# badge.net
KiCad netlist of a schematic drawn in EAGLE
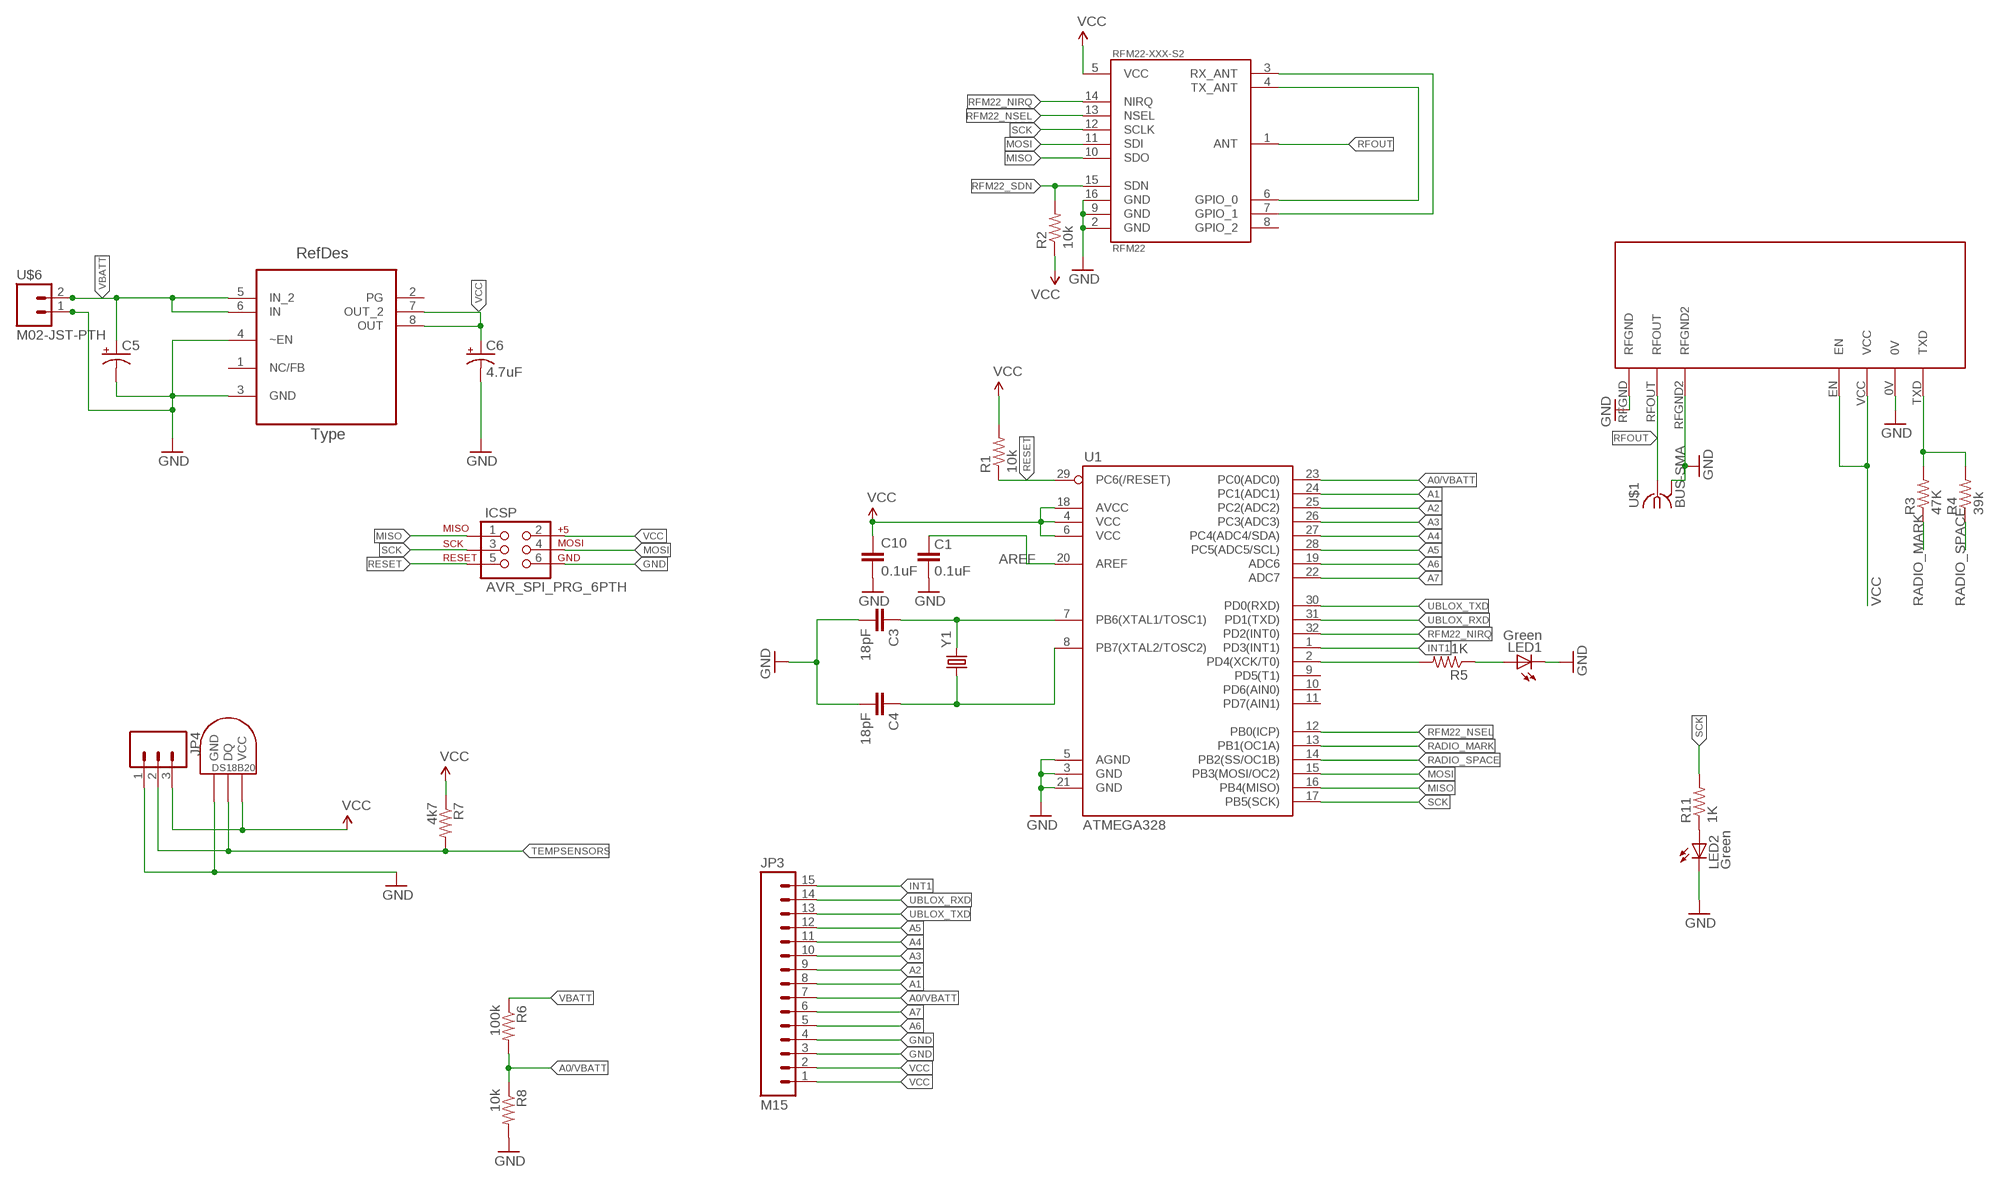
[diagram p0: schematic, sheet 1]

(export (version "E")
  (design (tool "Eeschema 10.0.6"))
  (components
    (comp (ref "C1")
      (value "0.1uF")
      (footprint "eagle-import:0603-CAP")
      (libsource (lib "eagle-import") (part "CAP0603-CAP"))
    )
    (comp (ref "C3")
      (value "18pF")
      (footprint "eagle-import:0603-CAP")
      (libsource (lib "eagle-import") (part "CAP0603-CAP"))
    )
    (comp (ref "C4")
      (value "18pF")
      (footprint "eagle-import:0603-CAP")
      (libsource (lib "eagle-import") (part "CAP0603-CAP"))
    )
    (comp (ref "C5")
      (value "CAP_POL1206-KIT")
      (footprint "eagle-import:EIA3216-KIT")
      (libsource (lib "eagle-import") (part "CAP_POL1206-KIT"))
    )
    (comp (ref "C6")
      (value "4.7uF")
      (footprint "eagle-import:EIA3216-KIT")
      (libsource (lib "eagle-import") (part "CAP_POL1206-KIT"))
    )
    (comp (ref "C10")
      (value "0.1uF")
      (footprint "eagle-import:0603-CAP")
      (libsource (lib "eagle-import") (part "CAP0603-CAP"))
    )
    (comp (ref "ICSP")
      (value "AVR_SPI_PRG_6PTH")
      (footprint "eagle-import:2X3")
      (libsource (lib "eagle-import") (part "AVR_SPI_PRG_6PTH"))
    )
    (comp (ref "JP3")
      (value "M15")
      (footprint "eagle-import:1X15")
      (libsource (lib "eagle-import") (part "M15"))
    )
    (comp (ref "JP4")
      (value "M03PTH")
      (footprint "eagle-import:1X03")
      (libsource (lib "eagle-import") (part "M03PTH"))
    )
    (comp (ref "LED1")
      (value "Green")
      (footprint "eagle-import:LED-0603")
      (libsource (lib "eagle-import") (part "LED0603"))
    )
    (comp (ref "LED2")
      (value "Green")
      (footprint "eagle-import:LED-0603")
      (libsource (lib "eagle-import") (part "LED0603"))
    )
    (comp (ref "NTX2TEMP")
      (value "DS1821")
      (footprint "eagle-import:DS18B20_SOIC")
      (libsource (lib "eagle-import") (part "DS1820SOIC"))
    )
    (comp (ref "R1")
      (value "10k")
      (footprint "eagle-import:0603-RES")
      (libsource (lib "eagle-import") (part "RESISTOR0603-RES"))
    )
    (comp (ref "R2")
      (value "10k")
      (footprint "eagle-import:0603-RES")
      (libsource (lib "eagle-import") (part "RESISTOR0603-RES"))
    )
    (comp (ref "R3")
      (value "47K")
      (footprint "eagle-import:0603-RES")
      (libsource (lib "eagle-import") (part "RESISTOR0603-RES"))
    )
    (comp (ref "R4")
      (value "39k")
      (footprint "eagle-import:0603-RES")
      (libsource (lib "eagle-import") (part "RESISTOR0603-RES"))
    )
    (comp (ref "R5")
      (value "1K")
      (footprint "eagle-import:0603-RES")
      (libsource (lib "eagle-import") (part "RESISTOR0603-RES"))
    )
    (comp (ref "R6")
      (value "100k")
      (footprint "eagle-import:0603-RES")
      (libsource (lib "eagle-import") (part "RESISTOR0603-RES"))
    )
    (comp (ref "R7")
      (value "4k7")
      (footprint "eagle-import:0603-RES")
      (libsource (lib "eagle-import") (part "RESISTOR0603-RES"))
    )
    (comp (ref "R8")
      (value "10k")
      (footprint "eagle-import:0603-RES")
      (libsource (lib "eagle-import") (part "RESISTOR0603-RES"))
    )
    (comp (ref "R11")
      (value "1K")
      (footprint "eagle-import:0603-RES")
      (libsource (lib "eagle-import") (part "RESISTOR0603-RES"))
    )
    (comp (ref "RFM22-XXX-S2")
      (value "RFM22")
      (footprint "eagle-import:RFM22-XXX-S2")
      (libsource (lib "eagle-import") (part "RFM22"))
    )
    (comp (ref "U$1")
      (value "BUS-SMA")
      (footprint "eagle-import:BUS-SMA")
      (libsource (lib "eagle-import") (part "BUS-SMA"))
    )
    (comp (ref "U$4")
      (value "NTX2")
      (footprint "eagle-import:NTX2")
      (libsource (lib "eagle-import") (part "NTX2"))
    )
    (comp (ref "U$6")
      (value "M02-JST-PTH")
      (footprint "eagle-import:M02-JST-PTH")
      (libsource (lib "eagle-import") (part "M02-JST-PTH"))
    )
    (comp (ref "U1")
      (value "ATMEGA328")
      (footprint "eagle-import:TQFP32-08")
      (libsource (lib "eagle-import") (part "ATMEGA168"))
    )
    (comp (ref "U2")
      (value "TPS76633D")
      (footprint "eagle-import:SOIC127P600X175-8N")
      (libsource (lib "eagle-import") (part "TPS76633D"))
    )
    (comp (ref "Y1")
      (value "CRYSTALSMD")
      (footprint "eagle-import:HC49UP")
      (libsource (lib "eagle-import") (part "CRYSTALSMD"))
    )
  )
  (nets
    (net (code "1") (name "/AREF") (class "Default")
      (node (ref "C1") (pin "2") (pinfunction "2_2") (pintype "passive"))
      (node (ref "U1") (pin "20") (pinfunction "AREF_20") (pintype "bidirectional"))
    )
    (net (code "2") (name "A0{slash}VBATT") (class "Default")
      (node (ref "JP3") (pin "7") (pinfunction "7_7") (pintype "passive"))
      (node (ref "R6") (pin "2") (pinfunction "2_2") (pintype "passive"))
      (node (ref "R8") (pin "1") (pinfunction "1_1") (pintype "passive"))
      (node (ref "U1") (pin "23") (pinfunction "PC0(ADC0)_23") (pintype "bidirectional"))
    )
    (net (code "3") (name "A1") (class "Default")
      (node (ref "JP3") (pin "8") (pinfunction "8_8") (pintype "passive"))
      (node (ref "U1") (pin "24") (pinfunction "PC1(ADC1)_24") (pintype "bidirectional"))
    )
    (net (code "4") (name "A2") (class "Default")
      (node (ref "JP3") (pin "9") (pinfunction "9_9") (pintype "passive"))
      (node (ref "U1") (pin "25") (pinfunction "PC2(ADC2)_25") (pintype "bidirectional"))
    )
    (net (code "5") (name "A3") (class "Default")
      (node (ref "JP3") (pin "10") (pinfunction "10_10") (pintype "passive"))
      (node (ref "U1") (pin "26") (pinfunction "PC3(ADC3)_26") (pintype "bidirectional"))
    )
    (net (code "6") (name "A4") (class "Default")
      (node (ref "JP3") (pin "11") (pinfunction "11_11") (pintype "passive"))
      (node (ref "U1") (pin "27") (pinfunction "PC4(ADC4/SDA)_27") (pintype "bidirectional"))
    )
    (net (code "7") (name "A5") (class "Default")
      (node (ref "JP3") (pin "12") (pinfunction "12_12") (pintype "passive"))
      (node (ref "U1") (pin "28") (pinfunction "PC5(ADC5/SCL)_28") (pintype "bidirectional"))
    )
    (net (code "8") (name "A6") (class "Default")
      (node (ref "JP3") (pin "5") (pinfunction "5_5") (pintype "passive"))
      (node (ref "U1") (pin "19") (pinfunction "ADC6_19") (pintype "bidirectional"))
    )
    (net (code "9") (name "A7") (class "Default")
      (node (ref "JP3") (pin "6") (pinfunction "6_6") (pintype "passive"))
      (node (ref "U1") (pin "22") (pinfunction "ADC7_22") (pintype "bidirectional"))
    )
    (net (code "10") (name "GND") (class "Default")
      (node (ref "C1") (pin "1") (pinfunction "1_1") (pintype "passive"))
      (node (ref "C10") (pin "2") (pinfunction "2_2") (pintype "passive"))
      (node (ref "C3") (pin "2") (pinfunction "2_2") (pintype "passive"))
      (node (ref "C4") (pin "2") (pinfunction "2_2") (pintype "passive"))
      (node (ref "C5") (pin "C") (pinfunction "-_C") (pintype "passive"))
      (node (ref "C6") (pin "C") (pinfunction "-_C") (pintype "passive"))
      (node (ref "ICSP") (pin "6") (pinfunction "6_6") (pintype "passive"))
      (node (ref "JP3") (pin "3") (pinfunction "3_3") (pintype "passive"))
      (node (ref "JP3") (pin "4") (pinfunction "4_4") (pintype "passive"))
      (node (ref "JP4") (pin "1") (pinfunction "1_1") (pintype "passive"))
      (node (ref "LED1") (pin "C") (pinfunction "C_C") (pintype "passive"))
      (node (ref "LED2") (pin "C") (pinfunction "C_C") (pintype "passive"))
      (node (ref "NTX2TEMP") (pin "GND") (pinfunction "GND_GND") (pintype "power_in"))
      (node (ref "R8") (pin "2") (pinfunction "2_2") (pintype "passive"))
      (node (ref "RFM22-XXX-S2") (pin "16") (pinfunction "GND_16") (pintype "power_in"))
      (node (ref "RFM22-XXX-S2") (pin "2") (pinfunction "GND_2") (pintype "power_in"))
      (node (ref "RFM22-XXX-S2") (pin "9") (pinfunction "GND_9") (pintype "power_in"))
      (node (ref "U$1") (pin "2") (pinfunction "GND_2") (pintype "power_in"))
      (node (ref "U$1") (pin "3") (pinfunction "GND_3") (pintype "power_in"))
      (node (ref "U$1") (pin "4") (pinfunction "GND_4") (pintype "power_in"))
      (node (ref "U$1") (pin "5") (pinfunction "GND_5") (pintype "power_in"))
      (node (ref "U$4") (pin "0V") (pinfunction "0V_0V") (pintype "bidirectional"))
      (node (ref "U$4") (pin "RFGND") (pinfunction "RFGND_RFGND") (pintype "bidirectional"))
      (node (ref "U$4") (pin "RFGND2") (pinfunction "RFGND2_RFGND2") (pintype "bidirectional"))
      (node (ref "U$6") (pin "1") (pinfunction "1_1") (pintype "passive"))
      (node (ref "U1") (pin "21") (pinfunction "GND_21") (pintype "bidirectional"))
      (node (ref "U1") (pin "3") (pinfunction "GND_3") (pintype "bidirectional"))
      (node (ref "U1") (pin "5") (pinfunction "AGND_5") (pintype "bidirectional"))
      (node (ref "U2") (pin "3") (pinfunction "GND_3") (pintype "passive"))
      (node (ref "U2") (pin "4") (pinfunction "~{EN}_4") (pintype "input"))
    )
    (net (code "11") (name "INT1") (class "Default")
      (node (ref "JP3") (pin "15") (pinfunction "15_15") (pintype "passive"))
      (node (ref "U1") (pin "1") (pinfunction "PD3(INT1)_1") (pintype "bidirectional"))
    )
    (net (code "12") (name "MISO") (class "Default")
      (node (ref "ICSP") (pin "1") (pinfunction "1_1") (pintype "passive"))
      (node (ref "RFM22-XXX-S2") (pin "10") (pinfunction "SDO_10") (pintype "output"))
      (node (ref "U1") (pin "16") (pinfunction "PB4(MISO)_16") (pintype "bidirectional"))
    )
    (net (code "13") (name "MOSI") (class "Default")
      (node (ref "ICSP") (pin "4") (pinfunction "4_4") (pintype "passive"))
      (node (ref "RFM22-XXX-S2") (pin "11") (pinfunction "SDI_11") (pintype "input"))
      (node (ref "U1") (pin "15") (pinfunction "PB3(MOSI/OC2)_15") (pintype "bidirectional"))
    )
    (net (code "14") (name "Net-(LED1-PadA)") (class "Default")
      (node (ref "LED1") (pin "A") (pinfunction "A_A") (pintype "passive"))
      (node (ref "R5") (pin "1") (pinfunction "1_1") (pintype "passive"))
    )
    (net (code "15") (name "Net-(LED2-PadA)") (class "Default")
      (node (ref "LED2") (pin "A") (pinfunction "A_A") (pintype "passive"))
      (node (ref "R11") (pin "1") (pinfunction "1_1") (pintype "passive"))
    )
    (net (code "16") (name "Net-(R3-Pad2)") (class "Default")
      (node (ref "R3") (pin "2") (pinfunction "2_2") (pintype "passive"))
      (node (ref "R4") (pin "2") (pinfunction "2_2") (pintype "passive"))
      (node (ref "U$4") (pin "TXD") (pinfunction "TXD_TXD") (pintype "bidirectional"))
    )
    (net (code "17") (name "Net-(RFM22-XXX-S2-GPIO_0)") (class "Default")
      (node (ref "RFM22-XXX-S2") (pin "4") (pinfunction "TX_ANT_4") (pintype "input"))
      (node (ref "RFM22-XXX-S2") (pin "6") (pinfunction "GPIO_0_6") (pintype "bidirectional"))
    )
    (net (code "18") (name "Net-(RFM22-XXX-S2-GPIO_1)") (class "Default")
      (node (ref "RFM22-XXX-S2") (pin "3") (pinfunction "RX_ANT_3") (pintype "input"))
      (node (ref "RFM22-XXX-S2") (pin "7") (pinfunction "GPIO_1_7") (pintype "bidirectional"))
    )
    (net (code "19") (name "Net-(U1-PB6(XTAL1{slash}TOSC1))") (class "Default")
      (node (ref "C3") (pin "1") (pinfunction "1_1") (pintype "passive"))
      (node (ref "U1") (pin "7") (pinfunction "PB6(XTAL1/TOSC1)_7") (pintype "bidirectional"))
      (node (ref "Y1") (pin "2") (pinfunction "2_2") (pintype "passive"))
    )
    (net (code "20") (name "Net-(U1-PB7(XTAL2{slash}TOSC2))") (class "Default")
      (node (ref "C4") (pin "1") (pinfunction "1_1") (pintype "passive"))
      (node (ref "U1") (pin "8") (pinfunction "PB7(XTAL2/TOSC2)_8") (pintype "bidirectional"))
      (node (ref "Y1") (pin "1") (pinfunction "1_1") (pintype "passive"))
    )
    (net (code "21") (name "Net-(U1-PD4(XCK{slash}T0))") (class "Default")
      (node (ref "R5") (pin "2") (pinfunction "2_2") (pintype "passive"))
      (node (ref "U1") (pin "2") (pinfunction "PD4(XCK/T0)_2") (pintype "bidirectional"))
    )
    (net (code "22") (name "RADIO_MARK") (class "Default")
      (node (ref "R3") (pin "1") (pinfunction "1_1") (pintype "passive"))
      (node (ref "U1") (pin "13") (pinfunction "PB1(OC1A)_13") (pintype "bidirectional"))
    )
    (net (code "23") (name "RADIO_SPACE") (class "Default")
      (node (ref "R4") (pin "1") (pinfunction "1_1") (pintype "passive"))
      (node (ref "U1") (pin "14") (pinfunction "PB2(SS/OC1B)_14") (pintype "bidirectional"))
    )
    (net (code "24") (name "RESET") (class "Default")
      (node (ref "ICSP") (pin "5") (pinfunction "5_5") (pintype "passive"))
      (node (ref "R1") (pin "1") (pinfunction "1_1") (pintype "passive"))
      (node (ref "U1") (pin "29") (pinfunction "PC6(/RESET)_29") (pintype "bidirectional"))
    )
    (net (code "25") (name "RFM22_NIRQ") (class "Default")
      (node (ref "RFM22-XXX-S2") (pin "14") (pinfunction "NIRQ_14") (pintype "output"))
      (node (ref "U1") (pin "32") (pinfunction "PD2(INT0)_32") (pintype "bidirectional"))
    )
    (net (code "26") (name "RFM22_NSEL") (class "Default")
      (node (ref "RFM22-XXX-S2") (pin "13") (pinfunction "NSEL_13") (pintype "input"))
      (node (ref "U1") (pin "12") (pinfunction "PB0(ICP)_12") (pintype "bidirectional"))
    )
    (net (code "27") (name "RFM22_SDN") (class "Default")
      (node (ref "R2") (pin "2") (pinfunction "2_2") (pintype "passive"))
      (node (ref "RFM22-XXX-S2") (pin "15") (pinfunction "SDN_15") (pintype "input"))
    )
    (net (code "28") (name "RFOUT") (class "Default")
      (node (ref "RFM22-XXX-S2") (pin "1") (pinfunction "ANT_1") (pintype "bidirectional"))
      (node (ref "U$1") (pin "1") (pinfunction "1_1") (pintype "passive"))
      (node (ref "U$4") (pin "RFOUT") (pinfunction "RFOUT_RFOUT") (pintype "bidirectional"))
    )
    (net (code "29") (name "SCK") (class "Default")
      (node (ref "ICSP") (pin "3") (pinfunction "3_3") (pintype "passive"))
      (node (ref "R11") (pin "2") (pinfunction "2_2") (pintype "passive"))
      (node (ref "RFM22-XXX-S2") (pin "12") (pinfunction "SCLK_12") (pintype "input"))
      (node (ref "U1") (pin "17") (pinfunction "PB5(SCK)_17") (pintype "bidirectional"))
    )
    (net (code "30") (name "TEMPSENSORS") (class "Default")
      (node (ref "JP4") (pin "2") (pinfunction "2_2") (pintype "passive"))
      (node (ref "NTX2TEMP") (pin "DQ") (pinfunction "DQ_DQ") (pintype "bidirectional"))
      (node (ref "R7") (pin "2") (pinfunction "2_2") (pintype "passive"))
    )
    (net (code "31") (name "UBLOX_RXD") (class "Default")
      (node (ref "JP3") (pin "14") (pinfunction "14_14") (pintype "passive"))
      (node (ref "U1") (pin "31") (pinfunction "PD1(TXD)_31") (pintype "bidirectional"))
    )
    (net (code "32") (name "UBLOX_TXD") (class "Default")
      (node (ref "JP3") (pin "13") (pinfunction "13_13") (pintype "passive"))
      (node (ref "U1") (pin "30") (pinfunction "PD0(RXD)_30") (pintype "bidirectional"))
    )
    (net (code "33") (name "VBATT") (class "Default")
      (node (ref "C5") (pin "A") (pinfunction "+_A") (pintype "passive"))
      (node (ref "R6") (pin "1") (pinfunction "1_1") (pintype "passive"))
      (node (ref "U$6") (pin "2") (pinfunction "2_2") (pintype "passive"))
      (node (ref "U2") (pin "5") (pinfunction "IN_2_5") (pintype "input"))
      (node (ref "U2") (pin "6") (pinfunction "IN_6") (pintype "input"))
    )
    (net (code "34") (name "VCC") (class "Default")
      (node (ref "C10") (pin "1") (pinfunction "1_1") (pintype "passive"))
      (node (ref "C6") (pin "A") (pinfunction "+_A") (pintype "passive"))
      (node (ref "ICSP") (pin "2") (pinfunction "2_2") (pintype "passive"))
      (node (ref "JP3") (pin "1") (pinfunction "1_1") (pintype "passive"))
      (node (ref "JP3") (pin "2") (pinfunction "2_2") (pintype "passive"))
      (node (ref "JP4") (pin "3") (pinfunction "3_3") (pintype "passive"))
      (node (ref "NTX2TEMP") (pin "VCC") (pinfunction "VCC_VCC") (pintype "power_in"))
      (node (ref "R1") (pin "2") (pinfunction "2_2") (pintype "passive"))
      (node (ref "R2") (pin "1") (pinfunction "1_1") (pintype "passive"))
      (node (ref "R7") (pin "1") (pinfunction "1_1") (pintype "passive"))
      (node (ref "RFM22-XXX-S2") (pin "5") (pinfunction "VCC_5") (pintype "bidirectional"))
      (node (ref "U$4") (pin "EN") (pinfunction "EN_EN") (pintype "bidirectional"))
      (node (ref "U$4") (pin "VCC") (pinfunction "VCC_VCC") (pintype "bidirectional"))
      (node (ref "U1") (pin "18") (pinfunction "AVCC_18") (pintype "bidirectional"))
      (node (ref "U1") (pin "4") (pinfunction "VCC_4") (pintype "bidirectional"))
      (node (ref "U1") (pin "6") (pinfunction "VCC_6") (pintype "bidirectional"))
      (node (ref "U2") (pin "7") (pinfunction "OUT_2_7") (pintype "output"))
      (node (ref "U2") (pin "8") (pinfunction "OUT_8") (pintype "output"))
    )
    (net (code "35") (name "unconnected-(RFM22-XXX-S2-GPIO_2-Pad8)") (class "Default")
      (node (ref "RFM22-XXX-S2") (pin "8") (pinfunction "GPIO_2_8") (pintype "bidirectional"))
    )
    (net (code "36") (name "unconnected-(U1-PD5(T1)-Pad9)") (class "Default")
      (node (ref "U1") (pin "9") (pinfunction "PD5(T1)_9") (pintype "bidirectional"))
    )
    (net (code "37") (name "unconnected-(U1-PD6(AIN0)-Pad10)") (class "Default")
      (node (ref "U1") (pin "10") (pinfunction "PD6(AIN0)_10") (pintype "bidirectional"))
    )
    (net (code "38") (name "unconnected-(U1-PD7(AIN1)-Pad11)") (class "Default")
      (node (ref "U1") (pin "11") (pinfunction "PD7(AIN1)_11") (pintype "bidirectional"))
    )
    (net (code "39") (name "unconnected-(U2-NC{slash}FB-Pad1)") (class "Default")
      (node (ref "U2") (pin "1") (pinfunction "NC/FB_1") (pintype "no_connect"))
    )
    (net (code "40") (name "unconnected-(U2-PG-Pad2)") (class "Default")
      (node (ref "U2") (pin "2") (pinfunction "PG_2") (pintype "output"))
    )
  )
)
